# Sheet1.net
KiCad netlist of a schematic drawn in Altium Designer
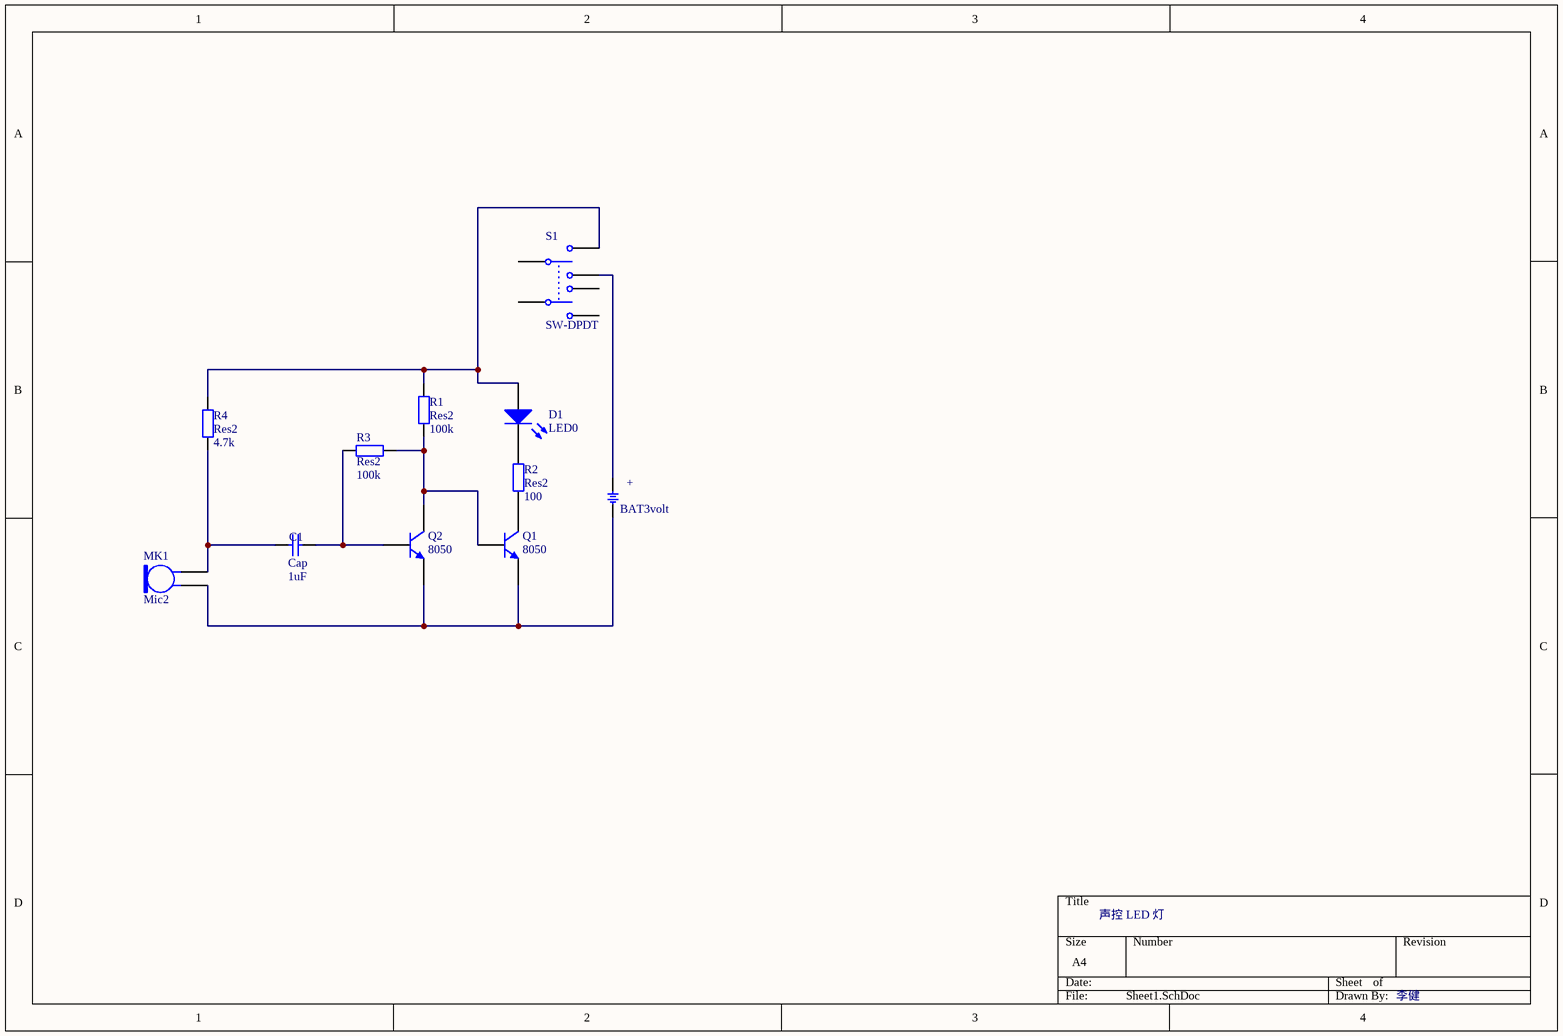
[diagram p0: Sheet1.SchDoc]

(export (version "E")
  (design (tool "Eeschema 10.0.6"))
  (components
    (comp (ref "BT1")
      (value "BAT3volt")
      (footprint "BTH2032")
      (description "BATTERY HOLDER, CR2032")
      (libsource (lib "BTH2032") (part "BATH_CR2032"))
    )
    (comp (ref "C1")
      (value "Cap")
      (footprint "RAD-0.2")
      (description "Capacitor")
      (fields (field (name "ALTIUM_VALUE") "1uF") (field (name "PUBLISHER") "Altium Limited"))
      (libsource (lib "Miscellaneous Devices") (part "Cap"))
    )
    (comp (ref "D1")
      (value "LED0")
      (footprint "LED-0")
      (description "Typical INFRARED GaAs LED")
      (fields (field (name "PUBLISHER") "Altium Limited"))
      (libsource (lib "Miscellaneous Devices") (part "LED0"))
    )
    (comp (ref "MK1")
      (value "Mic2")
      (footprint "PIN2")
      (description "Microphone")
      (fields (field (name "PUBLISHER") "Altium Limited"))
      (libsource (lib "Miscellaneous Devices") (part "Mic2"))
    )
    (comp (ref "Q1")
      (value "8050")
      (footprint "TO-92")
      (description "NPN General Purpose Amplifier")
      (fields (field (name "PUBLISHER") "Altium Limited"))
      (libsource (lib "Miscellaneous Devices") (part "2N3904"))
    )
    (comp (ref "Q2")
      (value "8050")
      (footprint "TO-92")
      (description "NPN General Purpose Amplifier")
      (fields (field (name "PUBLISHER") "Altium Limited"))
      (libsource (lib "Miscellaneous Devices") (part "2N3904"))
    )
    (comp (ref "R1")
      (value "Res2")
      (footprint "AXIAL-0.4")
      (description "Resistor")
      (fields (field (name "ALTIUM_VALUE") "100k") (field (name "PUBLISHER") "Altium Limited"))
      (libsource (lib "") (part "Res2_1"))
    )
    (comp (ref "R2")
      (value "Res2")
      (footprint "AXIAL-0.4")
      (description "Resistor")
      (fields (field (name "ALTIUM_VALUE") "100") (field (name "PUBLISHER") "Altium Limited"))
      (libsource (lib "") (part "Res2_1"))
    )
    (comp (ref "R3")
      (value "Res2")
      (footprint "AXIAL-0.4")
      (description "Resistor")
      (fields (field (name "ALTIUM_VALUE") "100k") (field (name "PUBLISHER") "Altium Limited"))
      (libsource (lib "Miscellaneous Devices") (part "Res2"))
    )
    (comp (ref "R4")
      (value "Res2")
      (footprint "AXIAL-0.4")
      (description "Resistor")
      (fields (field (name "ALTIUM_VALUE") "4.7k") (field (name "PUBLISHER") "Altium Limited"))
      (libsource (lib "") (part "Res2_1"))
    )
    (comp (ref "S1")
      (value "SW-DPDT")
      (footprint "DPDT-6")
      (description "Double-Pole, Double-Throw Switch")
      (fields (field (name "PUBLISHER") "Altium Limited"))
      (libsource (lib "Miscellaneous Devices") (part "SW-DPDT"))
    )
  )
  (nets
    (net (code "1") (name "Net-(BT1-Pad1)") (class "Default")
      (node (ref "BT1") (pin "1") (pinfunction "1_1") (pintype "passive"))
      (node (ref "S1") (pin "3") (pinfunction "3_3") (pintype "passive"))
    )
    (net (code "2") (name "Net-(C1-Pad1)") (class "Default")
      (node (ref "C1") (pin "1") (pinfunction "1_1") (pintype "passive"))
      (node (ref "MK1") (pin "2") (pinfunction "2_2") (pintype "passive"))
      (node (ref "R4") (pin "1") (pinfunction "1_1") (pintype "passive"))
    )
    (net (code "3") (name "Net-(D1-A)") (class "Default")
      (node (ref "D1") (pin "1") (pinfunction "A_1") (pintype "passive"))
      (node (ref "R1") (pin "2") (pinfunction "2_2") (pintype "passive"))
      (node (ref "R4") (pin "2") (pinfunction "2_2") (pintype "passive"))
      (node (ref "S1") (pin "2") (pinfunction "2_2") (pintype "passive"))
    )
    (net (code "4") (name "Net-(D1-K)") (class "Default")
      (node (ref "D1") (pin "2") (pinfunction "K_2") (pintype "passive"))
      (node (ref "R2") (pin "2") (pinfunction "2_2") (pintype "passive"))
    )
    (net (code "5") (name "Net-(Q1-B)") (class "Default")
      (node (ref "Q1") (pin "2") (pinfunction "B_2") (pintype "passive"))
      (node (ref "Q2") (pin "3") (pinfunction "C_3") (pintype "passive"))
      (node (ref "R1") (pin "1") (pinfunction "1_1") (pintype "passive"))
      (node (ref "R3") (pin "1") (pinfunction "1_1") (pintype "passive"))
    )
    (net (code "6") (name "Net-(Q1-C)") (class "Default")
      (node (ref "Q1") (pin "3") (pinfunction "C_3") (pintype "passive"))
      (node (ref "R2") (pin "1") (pinfunction "1_1") (pintype "passive"))
    )
    (net (code "7") (name "Net-(Q1-E)") (class "Default")
      (node (ref "BT1") (pin "2") (pinfunction "2_2") (pintype "passive"))
      (node (ref "MK1") (pin "1") (pinfunction "1_1") (pintype "passive"))
      (node (ref "Q1") (pin "1") (pinfunction "E_1") (pintype "passive"))
      (node (ref "Q2") (pin "1") (pinfunction "E_1") (pintype "passive"))
    )
    (net (code "8") (name "Net-(Q2-B)") (class "Default")
      (node (ref "C1") (pin "2") (pinfunction "2_2") (pintype "passive"))
      (node (ref "Q2") (pin "2") (pinfunction "B_2") (pintype "passive"))
      (node (ref "R3") (pin "2") (pinfunction "2_2") (pintype "passive"))
    )
    (net (code "9") (name "unconnected-(S1-Pad1)") (class "Default")
      (node (ref "S1") (pin "1") (pinfunction "1_1") (pintype "passive"))
    )
    (net (code "10") (name "unconnected-(S1-Pad4)") (class "Default")
      (node (ref "S1") (pin "4") (pinfunction "4_4") (pintype "passive"))
    )
    (net (code "11") (name "unconnected-(S1-Pad5)") (class "Default")
      (node (ref "S1") (pin "5") (pinfunction "5_5") (pintype "passive"))
    )
    (net (code "12") (name "unconnected-(S1-Pad6)") (class "Default")
      (node (ref "S1") (pin "6") (pinfunction "6_6") (pintype "passive"))
    )
  )
)
